# multifeedback_8k_lowpass.net
KiCad netlist of a schematic drawn in EAGLE
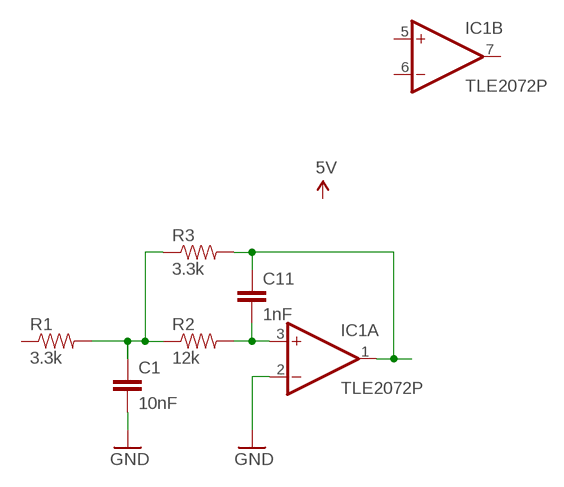
[diagram p0: schematic, sheet 1]

(export (version "E")
  (design (tool "Eeschema 10.0.6"))
  (components
    (comp (ref "C1")
      (value "10nF")
      (footprint "eagle-import:CAP-PTH-SMALL")
      (libsource (lib "eagle-import") (part "CAPPTH"))
    )
    (comp (ref "C11")
      (value "1nF")
      (footprint "eagle-import:CAP-PTH-SMALL")
      (libsource (lib "eagle-import") (part "CAPPTH"))
    )
    (comp (ref "IC1")
      (value "TLE2072P")
      (footprint "eagle-import:DIL08")
      (libsource (lib "eagle-import") (part "TLE2072P"))
    )
    (comp (ref "R1")
      (value "3.3k")
      (footprint "eagle-import:1_6W-RES")
      (libsource (lib "eagle-import") (part "RESISTORPTH-1/6W"))
    )
    (comp (ref "R2")
      (value "12k")
      (footprint "eagle-import:1_6W-RES")
      (libsource (lib "eagle-import") (part "RESISTORPTH-1/6W"))
    )
    (comp (ref "R3")
      (value "3.3k")
      (footprint "eagle-import:1_6W-RES")
      (libsource (lib "eagle-import") (part "RESISTORPTH-1/6W"))
    )
  )
  (nets
    (net (code "2") (name "GND") (class "Default")
      (node (ref "C1") (pin "2") (pinfunction "2_2") (pintype "passive"))
      (node (ref "IC1") (pin "2") (pinfunction "-IN_2") (pintype "input"))
    )
    (net (code "3") (name "Net-(C1-Pad1)") (class "Default")
      (node (ref "C1") (pin "1") (pinfunction "1_1") (pintype "passive"))
      (node (ref "R1") (pin "2") (pinfunction "2_2") (pintype "passive"))
      (node (ref "R2") (pin "1") (pinfunction "1_1") (pintype "passive"))
      (node (ref "R3") (pin "1") (pinfunction "1_1") (pintype "passive"))
    )
    (net (code "4") (name "Net-(IC1A-+IN)") (class "Default")
      (node (ref "C11") (pin "2") (pinfunction "2_2") (pintype "passive"))
      (node (ref "IC1") (pin "3") (pinfunction "+IN_3") (pintype "input"))
      (node (ref "R2") (pin "2") (pinfunction "2_2") (pintype "passive"))
    )
    (net (code "5") (name "Net-(IC1A-OUT)") (class "Default")
      (node (ref "C11") (pin "1") (pinfunction "1_1") (pintype "passive"))
      (node (ref "IC1") (pin "1") (pinfunction "OUT_1") (pintype "output"))
      (node (ref "R3") (pin "2") (pinfunction "2_2") (pintype "passive"))
    )
    (net (code "6") (name "unconnected-(IC1B-+IN-Pad5)") (class "Default")
      (node (ref "IC1") (pin "5") (pinfunction "+IN_5") (pintype "input"))
    )
    (net (code "7") (name "unconnected-(IC1B--IN-Pad6)") (class "Default")
      (node (ref "IC1") (pin "6") (pinfunction "-IN_6") (pintype "input"))
    )
    (net (code "8") (name "unconnected-(IC1B-OUT-Pad7)") (class "Default")
      (node (ref "IC1") (pin "7") (pinfunction "OUT_7") (pintype "output"))
    )
    (net (code "9") (name "unconnected-(R1-Pad1)") (class "Default")
      (node (ref "R1") (pin "1") (pinfunction "1_1") (pintype "passive"))
    )
  )
)
